# Card_Edge_Connecgtor.net
KiCad netlist of a schematic drawn in Altium Designer
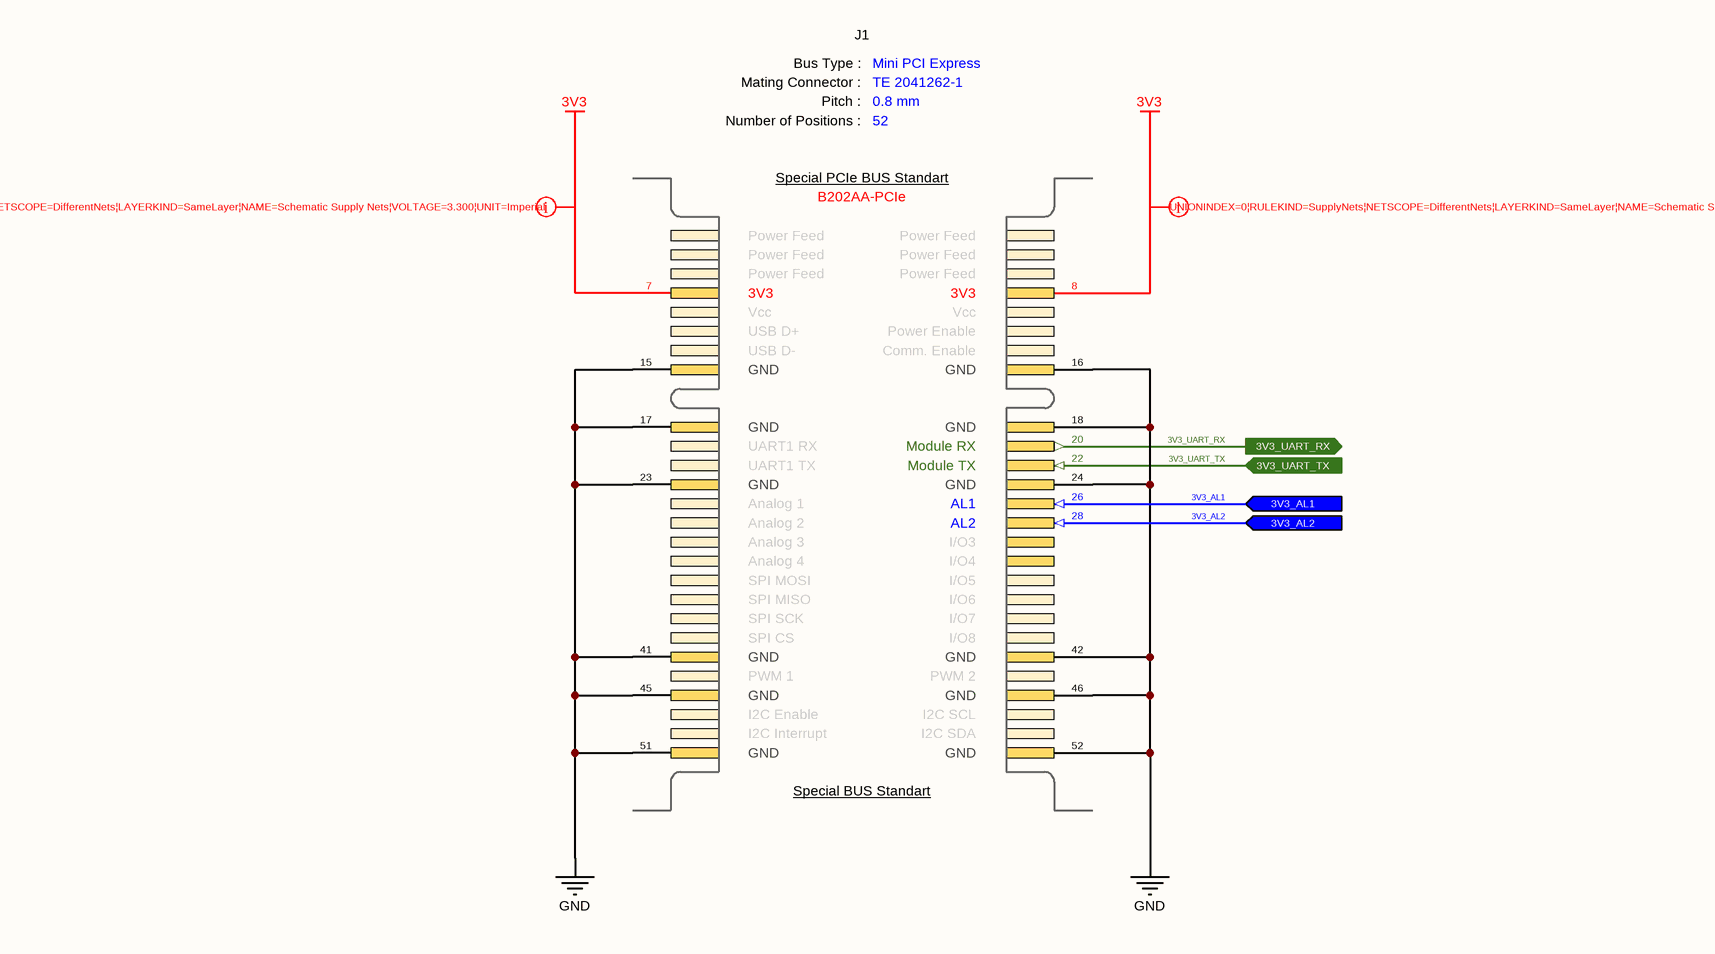
[diagram p0: Card Edge Connecgtor.SchDoc]

(export (version "E")
  (design (tool "Eeschema 10.0.6"))
  (components
    (comp (ref "J1")
      (value "Connector - Mini PCI-E (Male B202AA-PCIe)")
      (footprint "PCB - Mini PCI Express")
      (description "Mini PCI-Express gold finger connector.")
      (fields
        (field (name "BUS TYPE") "Mini PCI Express")
        (field (name "MATING CONNECTOR") "TE 2041262-1")
        (field (name "PITCH") "0.8 mm")
        (field (name "NUMBER OF POSITIONS") "52")
      )
      (libsource (lib "Akkoyun") (part "Connector - Mini PCI-E (Male B202AA-PCIe)"))
    )
  )
  (nets
    (net (code "1") (name "/3V3_AL1") (class "Default")
      (node (ref "J1") (pin "26") (pinfunction "Pin-26_26") (pintype "input"))
    )
    (net (code "2") (name "/3V3_AL2") (class "Default")
      (node (ref "J1") (pin "28") (pinfunction "Pin-28_28") (pintype "input"))
    )
    (net (code "3") (name "/3V3_UART_RX") (class "Default")
      (node (ref "J1") (pin "20") (pinfunction "Pin-20_20") (pintype "output"))
    )
    (net (code "4") (name "/3V3_UART_TX") (class "Default")
      (node (ref "J1") (pin "22") (pinfunction "Pin-22_22") (pintype "input"))
    )
    (net (code "5") (name "3V3") (class "Default")
      (node (ref "J1") (pin "7") (pinfunction "Pin-7_7") (pintype "power_in"))
      (node (ref "J1") (pin "8") (pinfunction "Pin-8_8") (pintype "power_in"))
    )
    (net (code "6") (name "GND") (class "Default")
      (node (ref "J1") (pin "15") (pinfunction "Pin-15_15") (pintype "power_in"))
      (node (ref "J1") (pin "16") (pinfunction "Pin-16_16") (pintype "power_in"))
      (node (ref "J1") (pin "17") (pinfunction "Pin-17_17") (pintype "power_in"))
      (node (ref "J1") (pin "18") (pinfunction "Pin-18_18") (pintype "power_in"))
      (node (ref "J1") (pin "23") (pinfunction "Pin-23_23") (pintype "power_in"))
      (node (ref "J1") (pin "24") (pinfunction "Pin-24_24") (pintype "power_in"))
      (node (ref "J1") (pin "41") (pinfunction "Pin-41_41") (pintype "power_in"))
      (node (ref "J1") (pin "42") (pinfunction "Pin-42_42") (pintype "power_in"))
      (node (ref "J1") (pin "45") (pinfunction "Pin-45_45") (pintype "power_in"))
      (node (ref "J1") (pin "46") (pinfunction "Pin-46_46") (pintype "power_in"))
      (node (ref "J1") (pin "51") (pinfunction "Pin-51_51") (pintype "power_in"))
      (node (ref "J1") (pin "52") (pinfunction "Pin-52_52") (pintype "power_in"))
    )
  )
)
